# room_auto_lock_V1_0.net
KiCad netlist of a schematic drawn in EAGLE
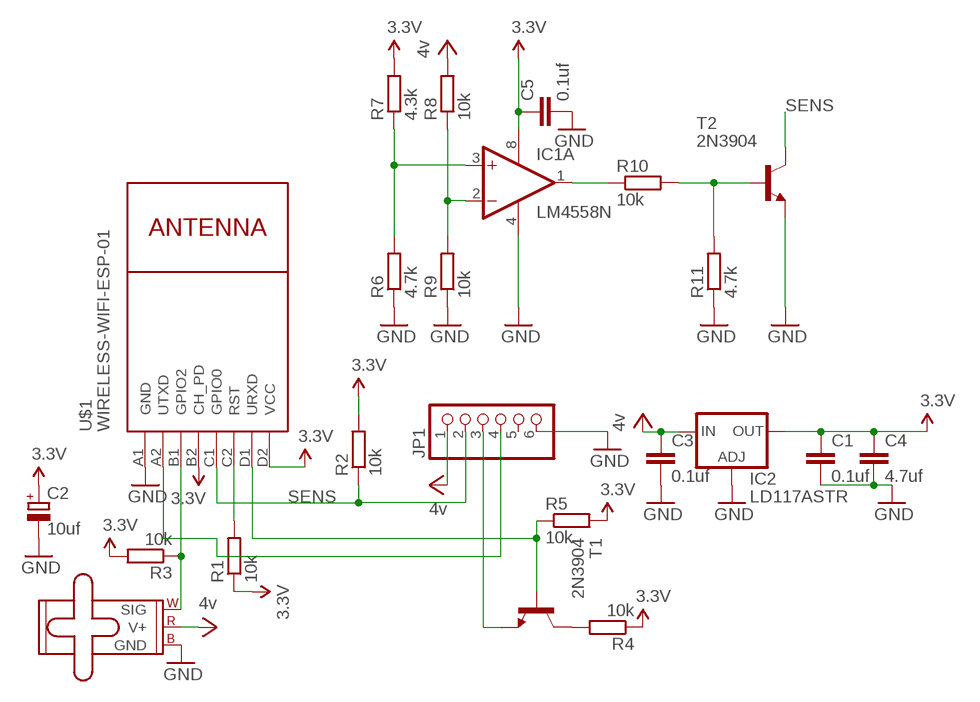
[diagram p0: schematic, sheet 1]

(export (version "E")
  (design (tool "Eeschema 10.0.6"))
  (components
    (comp (ref "C1")
      (value "0.1uf")
      (footprint "eagle-import:C0805")
      (libsource (lib "eagle-import") (part "C-EUC0805"))
    )
    (comp (ref "C2")
      (value "10uf")
      (footprint "eagle-import:E2,5-6")
      (libsource (lib "eagle-import") (part "CPOL-EUE2.5-6"))
    )
    (comp (ref "C3")
      (value "0.1uf")
      (footprint "eagle-import:C0805")
      (libsource (lib "eagle-import") (part "C-EUC0805"))
    )
    (comp (ref "C4")
      (value "4.7uf")
      (footprint "eagle-import:C1206K")
      (libsource (lib "eagle-import") (part "C-EUC1206K"))
    )
    (comp (ref "C5")
      (value "0.1uf")
      (footprint "eagle-import:C0805")
      (libsource (lib "eagle-import") (part "C-EUC0805"))
    )
    (comp (ref "IC1")
      (value "LM4558N")
      (footprint "eagle-import:DIL08")
      (libsource (lib "eagle-import") (part "4558NLM"))
    )
    (comp (ref "IC2")
      (value "LD117ASTR")
      (footprint "eagle-import:SOT223")
      (libsource (lib "eagle-import") (part "LD117A?STR"))
    )
    (comp (ref "JP1")
      (value "PINHD-1X6")
      (footprint "eagle-import:1X06")
      (libsource (lib "eagle-import") (part "PINHD-1X6"))
    )
    (comp (ref "M1")
      (value "SMALL_SERVO")
      (footprint "eagle-import:1X03")
      (libsource (lib "eagle-import") (part "SMALL_SERVO"))
    )
    (comp (ref "R1")
      (value "10k")
      (footprint "eagle-import:M2012")
      (libsource (lib "eagle-import") (part "R-EU_M2012"))
    )
    (comp (ref "R2")
      (value "10k")
      (footprint "eagle-import:M2012")
      (libsource (lib "eagle-import") (part "R-EU_M2012"))
    )
    (comp (ref "R3")
      (value "10k")
      (footprint "eagle-import:M2012")
      (libsource (lib "eagle-import") (part "R-EU_M2012"))
    )
    (comp (ref "R4")
      (value "10k")
      (footprint "eagle-import:M2012")
      (libsource (lib "eagle-import") (part "R-EU_M2012"))
    )
    (comp (ref "R5")
      (value "10k")
      (footprint "eagle-import:M2012")
      (libsource (lib "eagle-import") (part "R-EU_M2012"))
    )
    (comp (ref "R6")
      (value "4.7k")
      (footprint "eagle-import:0207_2V")
      (libsource (lib "eagle-import") (part "resistor_348_R-EU_0207/2V"))
    )
    (comp (ref "R7")
      (value "4.3k")
      (footprint "eagle-import:0207_2V")
      (libsource (lib "eagle-import") (part "resistor_348_R-EU_0207/2V"))
    )
    (comp (ref "R8")
      (value "10k")
      (footprint "eagle-import:R1206")
      (libsource (lib "eagle-import") (part "resistor_348_R-EU_R1206"))
    )
    (comp (ref "R9")
      (value "10k")
      (footprint "eagle-import:R1206")
      (libsource (lib "eagle-import") (part "resistor_348_R-EU_R1206"))
    )
    (comp (ref "R10")
      (value "10k")
      (footprint "eagle-import:R1206")
      (libsource (lib "eagle-import") (part "resistor_348_R-EU_R1206"))
    )
    (comp (ref "R11")
      (value "4.7k")
      (footprint "eagle-import:0207_10")
      (libsource (lib "eagle-import") (part "resistor_348_R-EU_0207/10"))
    )
    (comp (ref "T1")
      (value "2N3904")
      (footprint "eagle-import:TO92")
      (libsource (lib "eagle-import") (part "2N3904"))
    )
    (comp (ref "T2")
      (value "2N3904")
      (footprint "eagle-import:TO92")
      (libsource (lib "eagle-import") (part "2N3904"))
    )
    (comp (ref "U$1")
      (value "WIRELESS-WIFI-ESP-01")
      (footprint "eagle-import:WIRELESS-WIFI-ESP-01")
      (libsource (lib "eagle-import") (part "WIRELESS-WIFI-ESP-01"))
    )
  )
  (nets
    (net (code "1") (name "/SENS") (class "Default")
      (node (ref "JP1") (pin "2") (pinfunction "2_2") (pintype "passive"))
      (node (ref "R2") (pin "1") (pinfunction "1_1") (pintype "passive"))
      (node (ref "T2") (pin "1") (pinfunction "C_1") (pintype "passive"))
      (node (ref "U$1") (pin "C1") (pinfunction "GPIO0_C1") (pintype "bidirectional"))
    )
    (net (code "2") (name "3.3V") (class "Default")
      (node (ref "C1") (pin "1") (pinfunction "1_1") (pintype "passive"))
      (node (ref "C2") (pin "+") (pinfunction "+_+") (pintype "passive"))
      (node (ref "C4") (pin "1") (pinfunction "1_1") (pintype "passive"))
      (node (ref "C5") (pin "1") (pinfunction "1_1") (pintype "passive"))
      (node (ref "IC1") (pin "8") (pinfunction "V+_8") (pintype "power_in"))
      (node (ref "IC2") (pin "4") (pinfunction "OUT_4") (pintype "passive"))
      (node (ref "R1") (pin "1") (pinfunction "1_1") (pintype "passive"))
      (node (ref "R2") (pin "2") (pinfunction "2_2") (pintype "passive"))
      (node (ref "R3") (pin "2") (pinfunction "2_2") (pintype "passive"))
      (node (ref "R4") (pin "1") (pinfunction "1_1") (pintype "passive"))
      (node (ref "R5") (pin "2") (pinfunction "2_2") (pintype "passive"))
      (node (ref "R7") (pin "2") (pinfunction "2_2") (pintype "passive"))
      (node (ref "U$1") (pin "B2") (pinfunction "CH_PD_B2") (pintype "bidirectional"))
      (node (ref "U$1") (pin "D2") (pinfunction "VCC_D2") (pintype "power_in"))
    )
    (net (code "3") (name "4v") (class "Default")
      (node (ref "C3") (pin "1") (pinfunction "1_1") (pintype "passive"))
      (node (ref "IC2") (pin "3") (pinfunction "IN_3") (pintype "input"))
      (node (ref "JP1") (pin "1") (pinfunction "1_1") (pintype "passive"))
      (node (ref "M1") (pin "2") (pinfunction "V+_2") (pintype "bidirectional"))
      (node (ref "R8") (pin "2") (pinfunction "2_2") (pintype "passive"))
    )
    (net (code "4") (name "GND") (class "Default")
      (node (ref "C1") (pin "2") (pinfunction "2_2") (pintype "passive"))
      (node (ref "C2") (pin "-") (pinfunction "-_-") (pintype "passive"))
      (node (ref "C3") (pin "2") (pinfunction "2_2") (pintype "passive"))
      (node (ref "C4") (pin "2") (pinfunction "2_2") (pintype "passive"))
      (node (ref "C5") (pin "2") (pinfunction "2_2") (pintype "passive"))
      (node (ref "IC1") (pin "4") (pinfunction "V-_4") (pintype "power_in"))
      (node (ref "IC2") (pin "1") (pinfunction "ADJ_1") (pintype "input"))
      (node (ref "JP1") (pin "6") (pinfunction "6_6") (pintype "passive"))
      (node (ref "M1") (pin "3") (pinfunction "GND_3") (pintype "bidirectional"))
      (node (ref "R11") (pin "1") (pinfunction "1_1") (pintype "passive"))
      (node (ref "R6") (pin "1") (pinfunction "1_1") (pintype "passive"))
      (node (ref "R9") (pin "1") (pinfunction "1_1") (pintype "passive"))
      (node (ref "T2") (pin "3") (pinfunction "E_3") (pintype "passive"))
      (node (ref "U$1") (pin "A1") (pinfunction "GND_A1") (pintype "power_in"))
    )
    (net (code "5") (name "Net-(IC1A-+IN)") (class "Default")
      (node (ref "IC1") (pin "3") (pinfunction "+IN_3") (pintype "input"))
      (node (ref "R6") (pin "2") (pinfunction "2_2") (pintype "passive"))
      (node (ref "R7") (pin "1") (pinfunction "1_1") (pintype "passive"))
    )
    (net (code "6") (name "Net-(IC1A--IN)") (class "Default")
      (node (ref "IC1") (pin "2") (pinfunction "-IN_2") (pintype "input"))
      (node (ref "R8") (pin "1") (pinfunction "1_1") (pintype "passive"))
      (node (ref "R9") (pin "2") (pinfunction "2_2") (pintype "passive"))
    )
    (net (code "7") (name "Net-(IC1A-OUT)") (class "Default")
      (node (ref "IC1") (pin "1") (pinfunction "OUT_1") (pintype "output"))
      (node (ref "R10") (pin "1") (pinfunction "1_1") (pintype "passive"))
    )
    (net (code "8") (name "Net-(M1-SIG)") (class "Default")
      (node (ref "M1") (pin "1") (pinfunction "SIG_1") (pintype "bidirectional"))
      (node (ref "R3") (pin "1") (pinfunction "1_1") (pintype "passive"))
      (node (ref "U$1") (pin "B1") (pinfunction "GPIO2_B1") (pintype "bidirectional"))
    )
    (net (code "9") (name "Net-(T1-B)") (class "Default")
      (node (ref "R5") (pin "1") (pinfunction "1_1") (pintype "passive"))
      (node (ref "T1") (pin "2") (pinfunction "B_2") (pintype "passive"))
      (node (ref "U$1") (pin "D1") (pinfunction "URXD_D1") (pintype "bidirectional"))
    )
    (net (code "10") (name "Net-(T1-C)") (class "Default")
      (node (ref "R4") (pin "2") (pinfunction "2_2") (pintype "passive"))
      (node (ref "T1") (pin "1") (pinfunction "C_1") (pintype "passive"))
    )
    (net (code "11") (name "Net-(T1-E)") (class "Default")
      (node (ref "JP1") (pin "3") (pinfunction "3_3") (pintype "passive"))
      (node (ref "T1") (pin "3") (pinfunction "E_3") (pintype "passive"))
    )
    (net (code "12") (name "Net-(T2-B)") (class "Default")
      (node (ref "R10") (pin "2") (pinfunction "2_2") (pintype "passive"))
      (node (ref "R11") (pin "2") (pinfunction "2_2") (pintype "passive"))
      (node (ref "T2") (pin "2") (pinfunction "B_2") (pintype "passive"))
    )
    (net (code "13") (name "Net-(U$1-RST)") (class "Default")
      (node (ref "R1") (pin "2") (pinfunction "2_2") (pintype "passive"))
      (node (ref "U$1") (pin "C2") (pinfunction "RST_C2") (pintype "bidirectional"))
    )
    (net (code "14") (name "Net-(U$1-UTXD)") (class "Default")
      (node (ref "JP1") (pin "4") (pinfunction "4_4") (pintype "passive"))
      (node (ref "U$1") (pin "A2") (pinfunction "UTXD_A2") (pintype "bidirectional"))
    )
    (net (code "15") (name "unconnected-(JP1-Pad5)") (class "Default")
      (node (ref "JP1") (pin "5") (pinfunction "5_5") (pintype "passive"))
    )
  )
)
